# Main.net
KiCad netlist of a schematic drawn in Altium Designer
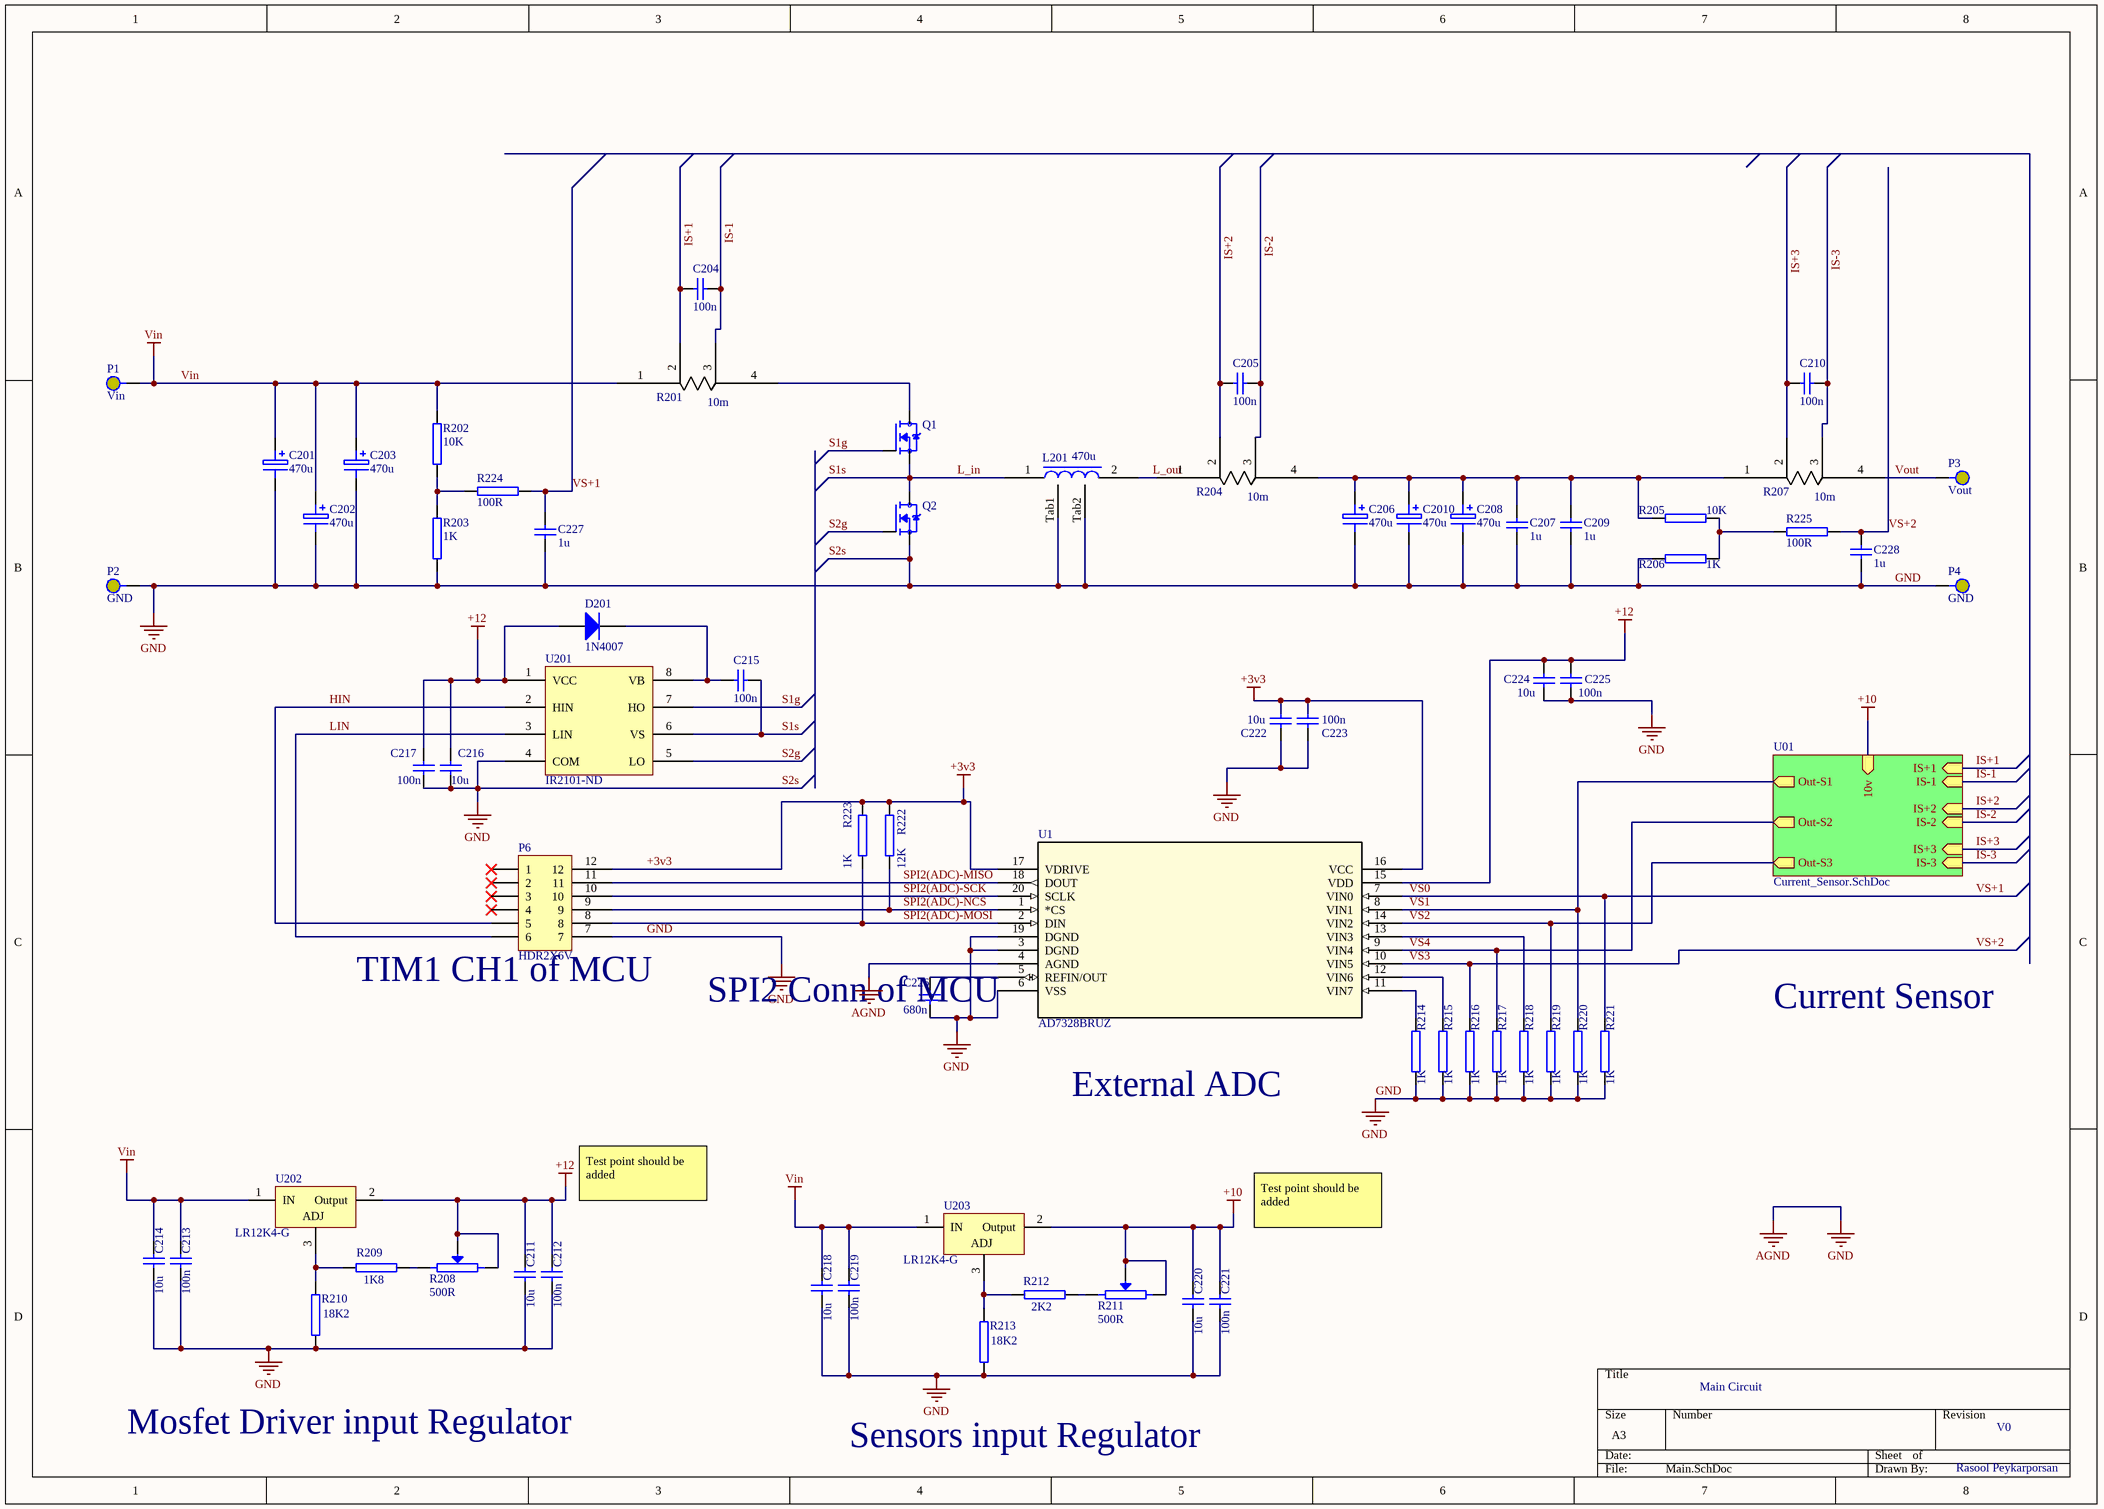
[diagram p0: Main.SchDoc]

(export (version "E")
  (design (tool "Eeschema 10.0.6"))
  (components
    (comp (ref "C201")
      (value "470u")
      (footprint "CAPP200-400_AUT")
      (description "Polarized Aluminum Capacitor, Through Hole, Pitch 200mil, Body 400mil (Dia)")
      (libsource (lib "Resistors and Capacitors") (part "CAPP200-400"))
    )
    (comp (ref "C202")
      (value "470u")
      (footprint "CAPP200-400_AUT")
      (description "Polarized Aluminum Capacitor, Through Hole, Pitch 200mil, Body 400mil (Dia)")
      (libsource (lib "Resistors and Capacitors") (part "CAPP200-400"))
    )
    (comp (ref "C203")
      (value "470u")
      (footprint "CAPP200-400_AUT")
      (description "Polarized Aluminum Capacitor, Through Hole, Pitch 200mil, Body 400mil (Dia)")
      (libsource (lib "Resistors and Capacitors") (part "CAPP200-400"))
    )
    (comp (ref "C204")
      (value "100n")
      (footprint "CAP_1206")
      (description "Non Polarized Capacitor, SMD, 1206")
      (libsource (lib "Resistors and Capacitors") (part "CAPN 1206"))
    )
    (comp (ref "C205")
      (value "100n")
      (footprint "CAP_1206")
      (description "Non Polarized Capacitor, SMD, 1206")
      (libsource (lib "Resistors and Capacitors") (part "CAPN 1206"))
    )
    (comp (ref "C206")
      (value "470u")
      (footprint "CAPP200-400_AUT")
      (description "Polarized Aluminum Capacitor, Through Hole, Pitch 200mil, Body 400mil (Dia)")
      (libsource (lib "Resistors and Capacitors") (part "CAPP200-400"))
    )
    (comp (ref "C207")
      (value "1u")
      (footprint "RAD-0.2_AUT")
      (description "Non Polarized Capacitor, Multilayer Ceramic Dipped Radial, Pitch 200mil")
      (libsource (lib "Resistors and Capacitors") (part "CAPN RAD0.2"))
    )
    (comp (ref "C208")
      (value "470u")
      (footprint "CAPP200-400_AUT")
      (description "Polarized Aluminum Capacitor, Through Hole, Pitch 200mil, Body 400mil (Dia)")
      (libsource (lib "Resistors and Capacitors") (part "CAPP200-400"))
    )
    (comp (ref "C209")
      (value "1u")
      (footprint "RAD-0.2_AUT")
      (description "Non Polarized Capacitor, Multilayer Ceramic Dipped Radial, Pitch 200mil")
      (libsource (lib "Resistors and Capacitors") (part "CAPN RAD0.2"))
    )
    (comp (ref "C210")
      (value "100n")
      (footprint "CAP_1206")
      (description "Non Polarized Capacitor, SMD, 1206")
      (libsource (lib "Resistors and Capacitors") (part "CAPN 1206"))
    )
    (comp (ref "C211")
      (value "10u")
      (footprint "CAP_1206")
      (description "Non Polarized Capacitor, SMD, 1206")
      (libsource (lib "Resistors and Capacitors") (part "CAPN 1206"))
    )
    (comp (ref "C212")
      (value "100n")
      (footprint "CAP_1206")
      (description "Non Polarized Capacitor, SMD, 1206")
      (libsource (lib "Resistors and Capacitors") (part "CAPN 1206"))
    )
    (comp (ref "C213")
      (value "100n")
      (footprint "CAP_1206")
      (description "Non Polarized Capacitor, SMD, 1206")
      (libsource (lib "Resistors and Capacitors") (part "CAPN 1206"))
    )
    (comp (ref "C214")
      (value "10u")
      (footprint "CAP_1206")
      (description "Non Polarized Capacitor, SMD, 1206")
      (libsource (lib "Resistors and Capacitors") (part "CAPN 1206"))
    )
    (comp (ref "C215")
      (value "100n")
      (footprint "RAD-0.2_AUT")
      (description "Non Polarized Capacitor, Multilayer Ceramic Dipped Radial, Pitch 200mil")
      (libsource (lib "Resistors and Capacitors") (part "CAPN RAD0.2"))
    )
    (comp (ref "C216")
      (value "10u")
      (footprint "CAP_1206")
      (description "Non Polarized Capacitor, SMD, 1206")
      (libsource (lib "Resistors and Capacitors") (part "CAPN 1206"))
    )
    (comp (ref "C217")
      (value "100n")
      (footprint "CAP_1206")
      (description "Non Polarized Capacitor, SMD, 1206")
      (libsource (lib "Resistors and Capacitors") (part "CAPN 1206"))
    )
    (comp (ref "C218")
      (value "10u")
      (footprint "CAP_1206")
      (description "Non Polarized Capacitor, SMD, 1206")
      (libsource (lib "Resistors and Capacitors") (part "CAPN 1206"))
    )
    (comp (ref "C219")
      (value "100n")
      (footprint "CAP_1206")
      (description "Non Polarized Capacitor, SMD, 1206")
      (libsource (lib "Resistors and Capacitors") (part "CAPN 1206"))
    )
    (comp (ref "C220")
      (value "10u")
      (footprint "CAP_1206")
      (description "Non Polarized Capacitor, SMD, 1206")
      (libsource (lib "Resistors and Capacitors") (part "CAPN 1206"))
    )
    (comp (ref "C221")
      (value "100n")
      (footprint "CAP_1206")
      (description "Non Polarized Capacitor, SMD, 1206")
      (libsource (lib "Resistors and Capacitors") (part "CAPN 1206"))
    )
    (comp (ref "C222")
      (value "10u")
      (footprint "CAP_1206")
      (description "Non Polarized Capacitor, SMD, 1206")
      (libsource (lib "Resistors and Capacitors") (part "CAPN 1206"))
    )
    (comp (ref "C223")
      (value "100n")
      (footprint "CAP_1206")
      (description "Non Polarized Capacitor, SMD, 1206")
      (libsource (lib "Resistors and Capacitors") (part "CAPN 1206"))
    )
    (comp (ref "C224")
      (value "10u")
      (footprint "CAP_1206")
      (description "Non Polarized Capacitor, SMD, 1206")
      (libsource (lib "Resistors and Capacitors") (part "CAPN 1206"))
    )
    (comp (ref "C225")
      (value "100n")
      (footprint "CAP_1206")
      (description "Non Polarized Capacitor, SMD, 1206")
      (libsource (lib "Resistors and Capacitors") (part "CAPN 1206"))
    )
    (comp (ref "C226")
      (value "680n")
      (footprint "CAP_1206")
      (description "Non Polarized Capacitor, SMD, 1206")
      (libsource (lib "Resistors and Capacitors") (part "CAPN 1206"))
    )
    (comp (ref "C227")
      (value "1u")
      (footprint "CAP_1206")
      (description "Non Polarized Capacitor, SMD, 1206")
      (libsource (lib "Resistors and Capacitors") (part "CAPN 1206"))
    )
    (comp (ref "C228")
      (value "1u")
      (footprint "CAP_1206")
      (description "Non Polarized Capacitor, SMD, 1206")
      (libsource (lib "Resistors and Capacitors") (part "CAPN 1206"))
    )
    (comp (ref "C2010")
      (value "470u")
      (footprint "CAPP200-400_AUT")
      (description "Polarized Aluminum Capacitor, Through Hole, Pitch 200mil, Body 400mil (Dia)")
      (libsource (lib "Resistors and Capacitors") (part "CAPP200-400"))
    )
    (comp (ref "D201")
      (value "1N4007")
      (footprint "DIODE0.4_AUT")
      (description "Diode, Standard, 1A, 1000v")
      (libsource (lib "Diodes") (part "1N4007"))
    )
    (comp (ref "L201")
      (value "470u")
      (footprint "AGP4233_Hi")
      (description "Power Inductor \r\nThrough hole")
      (libsource (lib "Projects_2025") (part "AGP4233Hi"))
    )
    (comp (ref "P1")
      (value "Vin")
      (footprint "Banana_AUT")
      (description "Banana Socket, 4mm, Panel, Black, 10A")
      (libsource (lib "Connectors") (part "Banana Socket"))
    )
    (comp (ref "P2")
      (value "GND")
      (footprint "Banana_AUT")
      (description "Banana Socket, 4mm, Panel, Black, 10A")
      (libsource (lib "Connectors") (part "Banana Socket"))
    )
    (comp (ref "P3")
      (value "Vout")
      (footprint "Banana_AUT")
      (description "Banana Socket, 4mm, Panel, Black, 10A")
      (libsource (lib "Connectors") (part "Banana Socket"))
    )
    (comp (ref "P4")
      (value "GND")
      (footprint "Banana_AUT")
      (description "Banana Socket, 4mm, Panel, Black, 10A")
      (libsource (lib "Connectors") (part "Banana Socket"))
    )
    (comp (ref "P6")
      (value "HDR2X6V")
      (footprint "HDR2X6V")
      (description "Header, 12-Pin, Dual row, 2.54mm Pitch, Straight")
      (libsource (lib "Schematics") (part "HDR2X6V"))
    )
    (comp (ref "Q1")
      (value "N-CHANNEL MOSFET,TOLL-8L")
      (footprint "TOLL-8L")
      (description "N-Channel 200 V 80A (Tc) 250W (Tj) Surface Mount TOLL-8L")
      (libsource (lib "Schematics") (part "MCTL80N20Y-TP"))
    )
    (comp (ref "Q2")
      (value "N-CHANNEL MOSFET,TOLL-8L")
      (footprint "TOLL-8L")
      (description "N-Channel 200 V 80A (Tc) 250W (Tj) Surface Mount TOLL-8L")
      (libsource (lib "Schematics") (part "MCTL80N20Y-TP"))
    )
    (comp (ref "R201")
      (value "10m")
      (footprint "WSL3673R_002-01")
      (description "Current Shunt \r\nKelvin 4W 0.002- 0.01")
      (libsource (lib "Projects_2025") (part "WSL3673R-01"))
    )
    (comp (ref "R202")
      (value "10K")
      (footprint "RES_1206")
      (description "Resistor, SMD, 1206")
      (libsource (lib "Resistors and Capacitors") (part "Resistor 1206"))
    )
    (comp (ref "R203")
      (value "1K")
      (footprint "RES_1206")
      (description "Resistor, SMD, 1206")
      (libsource (lib "Resistors and Capacitors") (part "Resistor 1206"))
    )
    (comp (ref "R204")
      (value "10m")
      (footprint "WSL3673R_002-01")
      (description "Current Shunt \r\nKelvin 4W 0.002- 0.01")
      (libsource (lib "Projects_2025") (part "WSL3673R-01"))
    )
    (comp (ref "R205")
      (value "10K")
      (footprint "RES_1206")
      (description "Resistor, SMD, 1206")
      (libsource (lib "Resistors and Capacitors") (part "Resistor 1206"))
    )
    (comp (ref "R206")
      (value "1K")
      (footprint "RES_1206")
      (description "Resistor, SMD, 1206")
      (libsource (lib "Resistors and Capacitors") (part "Resistor 1206"))
    )
    (comp (ref "R207")
      (value "10m")
      (footprint "WSL3673R_002-01")
      (description "Current Shunt \r\nKelvin 4W 0.002- 0.01")
      (libsource (lib "Projects_2025") (part "WSL3673R-01"))
    )
    (comp (ref "R208")
      (value "500R")
      (footprint "3296W")
      (libsource (lib "Potentiometers") (part "3296W-1-104LF"))
    )
    (comp (ref "R209")
      (value "1K8")
      (footprint "RES_1206")
      (description "Resistor, SMD, 1206")
      (libsource (lib "Resistors and Capacitors") (part "Resistor 1206"))
    )
    (comp (ref "R210")
      (value "18K2")
      (footprint "RES_1206")
      (description "Resistor, SMD, 1206")
      (libsource (lib "Resistors and Capacitors") (part "Resistor 1206"))
    )
    (comp (ref "R211")
      (value "500R")
      (footprint "3296W")
      (libsource (lib "Potentiometers") (part "3296W-1-104LF"))
    )
    (comp (ref "R212")
      (value "2K2")
      (footprint "RES_1206")
      (description "Resistor, SMD, 1206")
      (libsource (lib "Resistors and Capacitors") (part "Resistor 1206"))
    )
    (comp (ref "R213")
      (value "18K2")
      (footprint "RES_1206")
      (description "Resistor, SMD, 1206")
      (libsource (lib "Resistors and Capacitors") (part "Resistor 1206"))
    )
    (comp (ref "R214")
      (value "1K")
      (footprint "RES_1206")
      (description "Resistor, SMD, 1206")
      (libsource (lib "Resistors and Capacitors") (part "Resistor 1206"))
    )
    (comp (ref "R215")
      (value "1K")
      (footprint "RES_1206")
      (description "Resistor, SMD, 1206")
      (libsource (lib "Resistors and Capacitors") (part "Resistor 1206"))
    )
    (comp (ref "R216")
      (value "1K")
      (footprint "RES_1206")
      (description "Resistor, SMD, 1206")
      (libsource (lib "Resistors and Capacitors") (part "Resistor 1206"))
    )
    (comp (ref "R217")
      (value "1K")
      (footprint "RES_1206")
      (description "Resistor, SMD, 1206")
      (libsource (lib "Resistors and Capacitors") (part "Resistor 1206"))
    )
    (comp (ref "R218")
      (value "1K")
      (footprint "RES_1206")
      (description "Resistor, SMD, 1206")
      (libsource (lib "Resistors and Capacitors") (part "Resistor 1206"))
    )
    (comp (ref "R219")
      (value "1K")
      (footprint "RES_1206")
      (description "Resistor, SMD, 1206")
      (libsource (lib "Resistors and Capacitors") (part "Resistor 1206"))
    )
    (comp (ref "R220")
      (value "1K")
      (footprint "RES_1206")
      (description "Resistor, SMD, 1206")
      (libsource (lib "Resistors and Capacitors") (part "Resistor 1206"))
    )
    (comp (ref "R221")
      (value "1K")
      (footprint "RES_1206")
      (description "Resistor, SMD, 1206")
      (libsource (lib "Resistors and Capacitors") (part "Resistor 1206"))
    )
    (comp (ref "R222")
      (value "12K")
      (footprint "RES_1206")
      (description "Resistor, SMD, 1206")
      (libsource (lib "Resistors and Capacitors") (part "Resistor 1206"))
    )
    (comp (ref "R223")
      (value "1K")
      (footprint "RES_1206")
      (description "Resistor, SMD, 1206")
      (libsource (lib "Resistors and Capacitors") (part "Resistor 1206"))
    )
    (comp (ref "R224")
      (value "100R")
      (footprint "RES_1206")
      (description "Resistor, SMD, 1206")
      (libsource (lib "Resistors and Capacitors") (part "Resistor 1206"))
    )
    (comp (ref "R225")
      (value "100R")
      (footprint "RES_1206")
      (description "Resistor, SMD, 1206")
      (libsource (lib "Resistors and Capacitors") (part "Resistor 1206"))
    )
    (comp (ref "U1")
      (value "AD7328BRUZ")
      (footprint "TSSOP20_44")
      (description "ADC 12 Bit\r\nPackage TSSOP20")
      (libsource (lib "Projects_2025") (part "AD7328BRUZ"))
    )
    (comp (ref "U201")
      (value "IR2101-ND")
      (footprint "DIP8-AUT")
      (description "Half-Bridge Gate Driver IC Non-Inverting 8-PDIP")
      (libsource (lib "Schematics") (part "IR2101-ND"))
    )
    (comp (ref "U202")
      (value "LR12K4-G")
      (footprint "D PAK (TO-252-3)")
      (description "Adj Positive Regulator \r\nLinear. 12V dropout V. \r\n2W")
      (libsource (lib "Projects_2025") (part "LR12K4-G"))
    )
    (comp (ref "U203")
      (value "LR12K4-G")
      (footprint "D PAK (TO-252-3)")
      (description "Adj Positive Regulator \r\nLinear. 12V dropout V. \r\n2W")
      (libsource (lib "Projects_2025") (part "LR12K4-G"))
    )
  )
  (nets
    (net (code "1") (name "+3v3") (class "Default")
      (node (ref "C222") (pin "2") (pinfunction "2_2") (pintype "passive"))
      (node (ref "C223") (pin "2") (pinfunction "2_2") (pintype "passive"))
      (node (ref "P6") (pin "12") (pinfunction "12_12") (pintype "passive"))
      (node (ref "R222") (pin "2") (pinfunction "2_2") (pintype "passive"))
      (node (ref "R223") (pin "2") (pinfunction "2_2") (pintype "passive"))
      (node (ref "U1") (pin "16") (pinfunction "VCC_16") (pintype "power_in"))
      (node (ref "U1") (pin "17") (pinfunction "VDRIVE_17") (pintype "power_in"))
    )
    (net (code "2") (name "+10") (class "Default")
      (node (ref "C220") (pin "2") (pinfunction "2_2") (pintype "passive"))
      (node (ref "C221") (pin "2") (pinfunction "2_2") (pintype "passive"))
      (node (ref "R211") (pin "2") (pinfunction "BOT_2") (pintype "passive"))
      (node (ref "R211") (pin "W") (pinfunction "TAP_W") (pintype "passive"))
      (node (ref "U203") (pin "2") (pinfunction "Output_2") (pintype "power_in"))
    )
    (net (code "3") (name "+12") (class "Default")
      (node (ref "C211") (pin "2") (pinfunction "2_2") (pintype "passive"))
      (node (ref "C212") (pin "2") (pinfunction "2_2") (pintype "passive"))
      (node (ref "C216") (pin "2") (pinfunction "2_2") (pintype "passive"))
      (node (ref "C217") (pin "2") (pinfunction "2_2") (pintype "passive"))
      (node (ref "C224") (pin "2") (pinfunction "2_2") (pintype "passive"))
      (node (ref "C225") (pin "2") (pinfunction "2_2") (pintype "passive"))
      (node (ref "D201") (pin "A") (pinfunction "A_A") (pintype "passive"))
      (node (ref "R208") (pin "2") (pinfunction "BOT_2") (pintype "passive"))
      (node (ref "R208") (pin "W") (pinfunction "TAP_W") (pintype "passive"))
      (node (ref "U1") (pin "15") (pinfunction "VDD_15") (pintype "power_in"))
      (node (ref "U201") (pin "1") (pinfunction "VCC_1") (pintype "passive"))
      (node (ref "U202") (pin "2") (pinfunction "Output_2") (pintype "power_in"))
    )
    (net (code "4") (name "/HIN") (class "Default")
      (node (ref "P6") (pin "5") (pinfunction "5_5") (pintype "passive"))
      (node (ref "U201") (pin "2") (pinfunction "HIN_2") (pintype "passive"))
    )
    (net (code "5") (name "/IS+1") (class "Default")
      (node (ref "C204") (pin "1") (pinfunction "1_1") (pintype "passive"))
      (node (ref "R201") (pin "2") (pinfunction "2_2") (pintype "passive"))
    )
    (net (code "6") (name "/IS+2") (class "Default")
      (node (ref "C205") (pin "1") (pinfunction "1_1") (pintype "passive"))
      (node (ref "R204") (pin "2") (pinfunction "2_2") (pintype "passive"))
    )
    (net (code "7") (name "/IS+3") (class "Default")
      (node (ref "C210") (pin "1") (pinfunction "1_1") (pintype "passive"))
      (node (ref "R207") (pin "2") (pinfunction "2_2") (pintype "passive"))
    )
    (net (code "8") (name "/IS-1") (class "Default")
      (node (ref "C204") (pin "2") (pinfunction "2_2") (pintype "passive"))
      (node (ref "R201") (pin "3") (pinfunction "3_3") (pintype "passive"))
    )
    (net (code "9") (name "/IS-2") (class "Default")
      (node (ref "C205") (pin "2") (pinfunction "2_2") (pintype "passive"))
      (node (ref "R204") (pin "3") (pinfunction "3_3") (pintype "passive"))
    )
    (net (code "10") (name "/IS-3") (class "Default")
      (node (ref "C210") (pin "2") (pinfunction "2_2") (pintype "passive"))
      (node (ref "R207") (pin "3") (pinfunction "3_3") (pintype "passive"))
    )
    (net (code "11") (name "/LIN") (class "Default")
      (node (ref "P6") (pin "6") (pinfunction "6_6") (pintype "passive"))
      (node (ref "U201") (pin "3") (pinfunction "LIN_3") (pintype "passive"))
    )
    (net (code "12") (name "/L_in") (class "Default")
      (node (ref "C215") (pin "2") (pinfunction "2_2") (pintype "passive"))
      (node (ref "L201") (pin "1") (pinfunction "1_1") (pintype "passive"))
      (node (ref "Q1") (pin "2") (pinfunction "S_2") (pintype "passive"))
      (node (ref "Q2") (pin "3") (pinfunction "D_3") (pintype "passive"))
      (node (ref "U201") (pin "6") (pinfunction "VS_6") (pintype "passive"))
    )
    (net (code "13") (name "/L_out") (class "Default")
      (node (ref "L201") (pin "2") (pinfunction "2_2") (pintype "passive"))
      (node (ref "R204") (pin "1") (pinfunction "1_1") (pintype "passive"))
    )
    (net (code "14") (name "/S1g") (class "Default")
      (node (ref "Q1") (pin "1") (pinfunction "G_1") (pintype "passive"))
      (node (ref "U201") (pin "7") (pinfunction "HO_7") (pintype "passive"))
    )
    (net (code "15") (name "/S2g") (class "Default")
      (node (ref "Q2") (pin "1") (pinfunction "G_1") (pintype "passive"))
      (node (ref "U201") (pin "5") (pinfunction "LO_5") (pintype "passive"))
    )
    (net (code "16") (name "/SPI2(ADC)-MISO") (class "Default")
      (node (ref "P6") (pin "11") (pinfunction "11_11") (pintype "passive"))
      (node (ref "U1") (pin "18") (pinfunction "DOUT_18") (pintype "output"))
    )
    (net (code "17") (name "/SPI2(ADC)-MOSI") (class "Default")
      (node (ref "P6") (pin "8") (pinfunction "8_8") (pintype "passive"))
      (node (ref "R223") (pin "1") (pinfunction "1_1") (pintype "passive"))
      (node (ref "U1") (pin "2") (pinfunction "DIN_2") (pintype "input"))
    )
    (net (code "18") (name "/SPI2(ADC)-NCS") (class "Default")
      (node (ref "P6") (pin "9") (pinfunction "9_9") (pintype "passive"))
      (node (ref "R222") (pin "1") (pinfunction "1_1") (pintype "passive"))
      (node (ref "U1") (pin "1") (pinfunction "*CS_1") (pintype "input"))
    )
    (net (code "19") (name "/SPI2(ADC)-SCK") (class "Default")
      (node (ref "P6") (pin "10") (pinfunction "10_10") (pintype "passive"))
      (node (ref "U1") (pin "20") (pinfunction "SCLK_20") (pintype "input"))
    )
    (net (code "20") (name "/VS+1") (class "Default")
      (node (ref "C227") (pin "2") (pinfunction "2_2") (pintype "passive"))
      (node (ref "R221") (pin "2") (pinfunction "2_2") (pintype "passive"))
      (node (ref "R224") (pin "2") (pinfunction "2_2") (pintype "passive"))
      (node (ref "U1") (pin "7") (pinfunction "VIN0_7") (pintype "input"))
    )
    (net (code "21") (name "/VS+2") (class "Default")
      (node (ref "C228") (pin "2") (pinfunction "2_2") (pintype "passive"))
      (node (ref "R216") (pin "2") (pinfunction "2_2") (pintype "passive"))
      (node (ref "R225") (pin "2") (pinfunction "2_2") (pintype "passive"))
      (node (ref "U1") (pin "10") (pinfunction "VIN5_10") (pintype "input"))
    )
    (net (code "22") (name "/VS1") (class "Default")
      (node (ref "R220") (pin "2") (pinfunction "2_2") (pintype "passive"))
      (node (ref "U1") (pin "8") (pinfunction "VIN1_8") (pintype "input"))
    )
    (net (code "23") (name "/VS2") (class "Default")
      (node (ref "R219") (pin "2") (pinfunction "2_2") (pintype "passive"))
      (node (ref "U1") (pin "14") (pinfunction "VIN2_14") (pintype "input"))
    )
    (net (code "24") (name "/VS4") (class "Default")
      (node (ref "R217") (pin "2") (pinfunction "2_2") (pintype "passive"))
      (node (ref "U1") (pin "9") (pinfunction "VIN4_9") (pintype "input"))
    )
    (net (code "25") (name "/Vout") (class "Default")
      (node (ref "P3") (pin "1") (pintype "passive"))
      (node (ref "R207") (pin "4") (pinfunction "4_4") (pintype "passive"))
    )
    (net (code "26") (name "AGND") (class "Default")
      (node (ref "C201") (pin "2") (pinfunction "2_2") (pintype "passive"))
      (node (ref "C2010") (pin "2") (pinfunction "2_2") (pintype "passive"))
      (node (ref "C202") (pin "2") (pinfunction "2_2") (pintype "passive"))
      (node (ref "C203") (pin "2") (pinfunction "2_2") (pintype "passive"))
      (node (ref "C206") (pin "2") (pinfunction "2_2") (pintype "passive"))
      (node (ref "C207") (pin "1") (pinfunction "1_1") (pintype "passive"))
      (node (ref "C208") (pin "2") (pinfunction "2_2") (pintype "passive"))
      (node (ref "C209") (pin "1") (pinfunction "1_1") (pintype "passive"))
      (node (ref "C211") (pin "1") (pinfunction "1_1") (pintype "passive"))
      (node (ref "C212") (pin "1") (pinfunction "1_1") (pintype "passive"))
      (node (ref "C213") (pin "1") (pinfunction "1_1") (pintype "passive"))
      (node (ref "C214") (pin "1") (pinfunction "1_1") (pintype "passive"))
      (node (ref "C216") (pin "1") (pinfunction "1_1") (pintype "passive"))
      (node (ref "C217") (pin "1") (pinfunction "1_1") (pintype "passive"))
      (node (ref "C218") (pin "1") (pinfunction "1_1") (pintype "passive"))
      (node (ref "C219") (pin "1") (pinfunction "1_1") (pintype "passive"))
      (node (ref "C220") (pin "1") (pinfunction "1_1") (pintype "passive"))
      (node (ref "C221") (pin "1") (pinfunction "1_1") (pintype "passive"))
      (node (ref "C222") (pin "1") (pinfunction "1_1") (pintype "passive"))
      (node (ref "C223") (pin "1") (pinfunction "1_1") (pintype "passive"))
      (node (ref "C224") (pin "1") (pinfunction "1_1") (pintype "passive"))
      (node (ref "C225") (pin "1") (pinfunction "1_1") (pintype "passive"))
      (node (ref "C226") (pin "1") (pinfunction "1_1") (pintype "passive"))
      (node (ref "C227") (pin "1") (pinfunction "1_1") (pintype "passive"))
      (node (ref "C228") (pin "1") (pinfunction "1_1") (pintype "passive"))
      (node (ref "L201") (pin "Tab1") (pinfunction "Tab1_Tab1") (pintype "passive"))
      (node (ref "L201") (pin "Tab2") (pinfunction "Tab2_Tab2") (pintype "passive"))
      (node (ref "P2") (pin "1") (pintype "passive"))
      (node (ref "P4") (pin "1") (pintype "passive"))
      (node (ref "P6") (pin "7") (pinfunction "7_7") (pintype "passive"))
      (node (ref "Q2") (pin "2") (pinfunction "S_2") (pintype "passive"))
      (node (ref "R203") (pin "2") (pinfunction "2_2") (pintype "passive"))
      (node (ref "R206") (pin "1") (pinfunction "1_1") (pintype "passive"))
      (node (ref "R210") (pin "1") (pinfunction "1_1") (pintype "passive"))
      (node (ref "R213") (pin "1") (pinfunction "1_1") (pintype "passive"))
      (node (ref "R214") (pin "1") (pinfunction "1_1") (pintype "passive"))
      (node (ref "R215") (pin "1") (pinfunction "1_1") (pintype "passive"))
      (node (ref "R216") (pin "1") (pinfunction "1_1") (pintype "passive"))
      (node (ref "R217") (pin "1") (pinfunction "1_1") (pintype "passive"))
      (node (ref "R218") (pin "1") (pinfunction "1_1") (pintype "passive"))
      (node (ref "R219") (pin "1") (pinfunction "1_1") (pintype "passive"))
      (node (ref "R220") (pin "1") (pinfunction "1_1") (pintype "passive"))
      (node (ref "R221") (pin "1") (pinfunction "1_1") (pintype "passive"))
      (node (ref "U1") (pin "19") (pinfunction "DGND_19") (pintype "power_in"))
      (node (ref "U1") (pin "3") (pinfunction "DGND_3") (pintype "power_in"))
      (node (ref "U1") (pin "4") (pinfunction "AGND_4") (pintype "power_in"))
      (node (ref "U1") (pin "6") (pinfunction "VSS_6") (pintype "power_in"))
      (node (ref "U201") (pin "4") (pinfunction "COM_4") (pintype "passive"))
    )
    (net (code "27") (name "Net-(C2010-Pad1)") (class "Default")
      (node (ref "C2010") (pin "1") (pinfunction "1_1") (pintype "passive"))
      (node (ref "C206") (pin "1") (pinfunction "1_1") (pintype "passive"))
      (node (ref "C207") (pin "2") (pinfunction "2_2") (pintype "passive"))
      (node (ref "C208") (pin "1") (pinfunction "1_1") (pintype "passive"))
      (node (ref "C209") (pin "2") (pinfunction "2_2") (pintype "passive"))
      (node (ref "R204") (pin "4") (pinfunction "4_4") (pintype "passive"))
      (node (ref "R205") (pin "1") (pinfunction "1_1") (pintype "passive"))
      (node (ref "R207") (pin "1") (pinfunction "1_1") (pintype "passive"))
    )
    (net (code "28") (name "Net-(Q1-D)") (class "Default")
      (node (ref "Q1") (pin "3") (pinfunction "D_3") (pintype "passive"))
      (node (ref "R201") (pin "4") (pinfunction "4_4") (pintype "passive"))
    )
    (net (code "29") (name "Net-(R202-Pad2)") (class "Default")
      (node (ref "R202") (pin "2") (pinfunction "2_2") (pintype "passive"))
      (node (ref "R203") (pin "1") (pinfunction "1_1") (pintype "passive"))
      (node (ref "R224") (pin "1") (pinfunction "1_1") (pintype "passive"))
    )
    (net (code "30") (name "Net-(R205-Pad2)") (class "Default")
      (node (ref "R205") (pin "2") (pinfunction "2_2") (pintype "passive"))
      (node (ref "R206") (pin "2") (pinfunction "2_2") (pintype "passive"))
      (node (ref "R225") (pin "1") (pinfunction "1_1") (pintype "passive"))
    )
    (net (code "31") (name "Net-(R208-TOP)") (class "Default")
      (node (ref "R208") (pin "1") (pinfunction "TOP_1") (pintype "passive"))
      (node (ref "R209") (pin "1") (pinfunction "1_1") (pintype "passive"))
    )
    (net (code "32") (name "Net-(R211-TOP)") (class "Default")
      (node (ref "R211") (pin "1") (pinfunction "TOP_1") (pintype "passive"))
      (node (ref "R212") (pin "1") (pinfunction "1_1") (pintype "passive"))
    )
    (net (code "33") (name "Net-(U1-REFIN{slash}OUT)") (class "Default")
      (node (ref "C226") (pin "2") (pinfunction "2_2") (pintype "passive"))
      (node (ref "U1") (pin "5") (pinfunction "REFIN/OUT_5") (pintype "bidirectional"))
    )
    (net (code "34") (name "Net-(U1-VIN3)") (class "Default")
      (node (ref "R218") (pin "2") (pinfunction "2_2") (pintype "passive"))
      (node (ref "U1") (pin "13") (pinfunction "VIN3_13") (pintype "input"))
    )
    (net (code "35") (name "Net-(U1-VIN6)") (class "Default")
      (node (ref "R215") (pin "2") (pinfunction "2_2") (pintype "passive"))
      (node (ref "U1") (pin "12") (pinfunction "VIN6_12") (pintype "input"))
    )
    (net (code "36") (name "Net-(U1-VIN7)") (class "Default")
      (node (ref "R214") (pin "2") (pinfunction "2_2") (pintype "passive"))
      (node (ref "U1") (pin "11") (pinfunction "VIN7_11") (pintype "input"))
    )
    (net (code "37") (name "Net-(U201-VB)") (class "Default")
      (node (ref "C215") (pin "1") (pinfunction "1_1") (pintype "passive"))
      (node (ref "D201") (pin "K") (pinfunction "K_K") (pintype "passive"))
      (node (ref "U201") (pin "8") (pinfunction "VB_8") (pintype "passive"))
    )
    (net (code "38") (name "Net-(U202-ADJ)") (class "Default")
      (node (ref "R209") (pin "2") (pinfunction "2_2") (pintype "passive"))
      (node (ref "R210") (pin "2") (pinfunction "2_2") (pintype "passive"))
      (node (ref "U202") (pin "3") (pinfunction "ADJ_3") (pintype "power_in"))
    )
    (net (code "39") (name "Net-(U203-ADJ)") (class "Default")
      (node (ref "R212") (pin "2") (pinfunction "2_2") (pintype "passive"))
      (node (ref "R213") (pin "2") (pinfunction "2_2") (pintype "passive"))
      (node (ref "U203") (pin "3") (pinfunction "ADJ_3") (pintype "power_in"))
    )
    (net (code "40") (name "Vin") (class "Default")
      (node (ref "C201") (pin "1") (pinfunction "1_1") (pintype "passive"))
      (node (ref "C202") (pin "1") (pinfunction "1_1") (pintype "passive"))
      (node (ref "C203") (pin "1") (pinfunction "1_1") (pintype "passive"))
      (node (ref "C213") (pin "2") (pinfunction "2_2") (pintype "passive"))
      (node (ref "C214") (pin "2") (pinfunction "2_2") (pintype "passive"))
      (node (ref "C218") (pin "2") (pinfunction "2_2") (pintype "passive"))
      (node (ref "C219") (pin "2") (pinfunction "2_2") (pintype "passive"))
      (node (ref "P1") (pin "1") (pintype "passive"))
      (node (ref "R201") (pin "1") (pinfunction "1_1") (pintype "passive"))
      (node (ref "R202") (pin "1") (pinfunction "1_1") (pintype "passive"))
      (node (ref "U202") (pin "1") (pinfunction "IN_1") (pintype "power_in"))
      (node (ref "U203") (pin "1") (pinfunction "IN_1") (pintype "power_in"))
    )
    (net (code "41") (name "unconnected-(P6-Pad1)") (class "Default")
      (node (ref "P6") (pin "1") (pinfunction "1_1") (pintype "passive+no_connect"))
    )
    (net (code "42") (name "unconnected-(P6-Pad2)") (class "Default")
      (node (ref "P6") (pin "2") (pinfunction "2_2") (pintype "passive+no_connect"))
    )
    (net (code "43") (name "unconnected-(P6-Pad3)") (class "Default")
      (node (ref "P6") (pin "3") (pinfunction "3_3") (pintype "passive+no_connect"))
    )
    (net (code "44") (name "unconnected-(P6-Pad4)") (class "Default")
      (node (ref "P6") (pin "4") (pinfunction "4_4") (pintype "passive+no_connect"))
    )
  )
)
